# microBoard_DRV8842.net
KiCad netlist of a schematic drawn in EAGLE
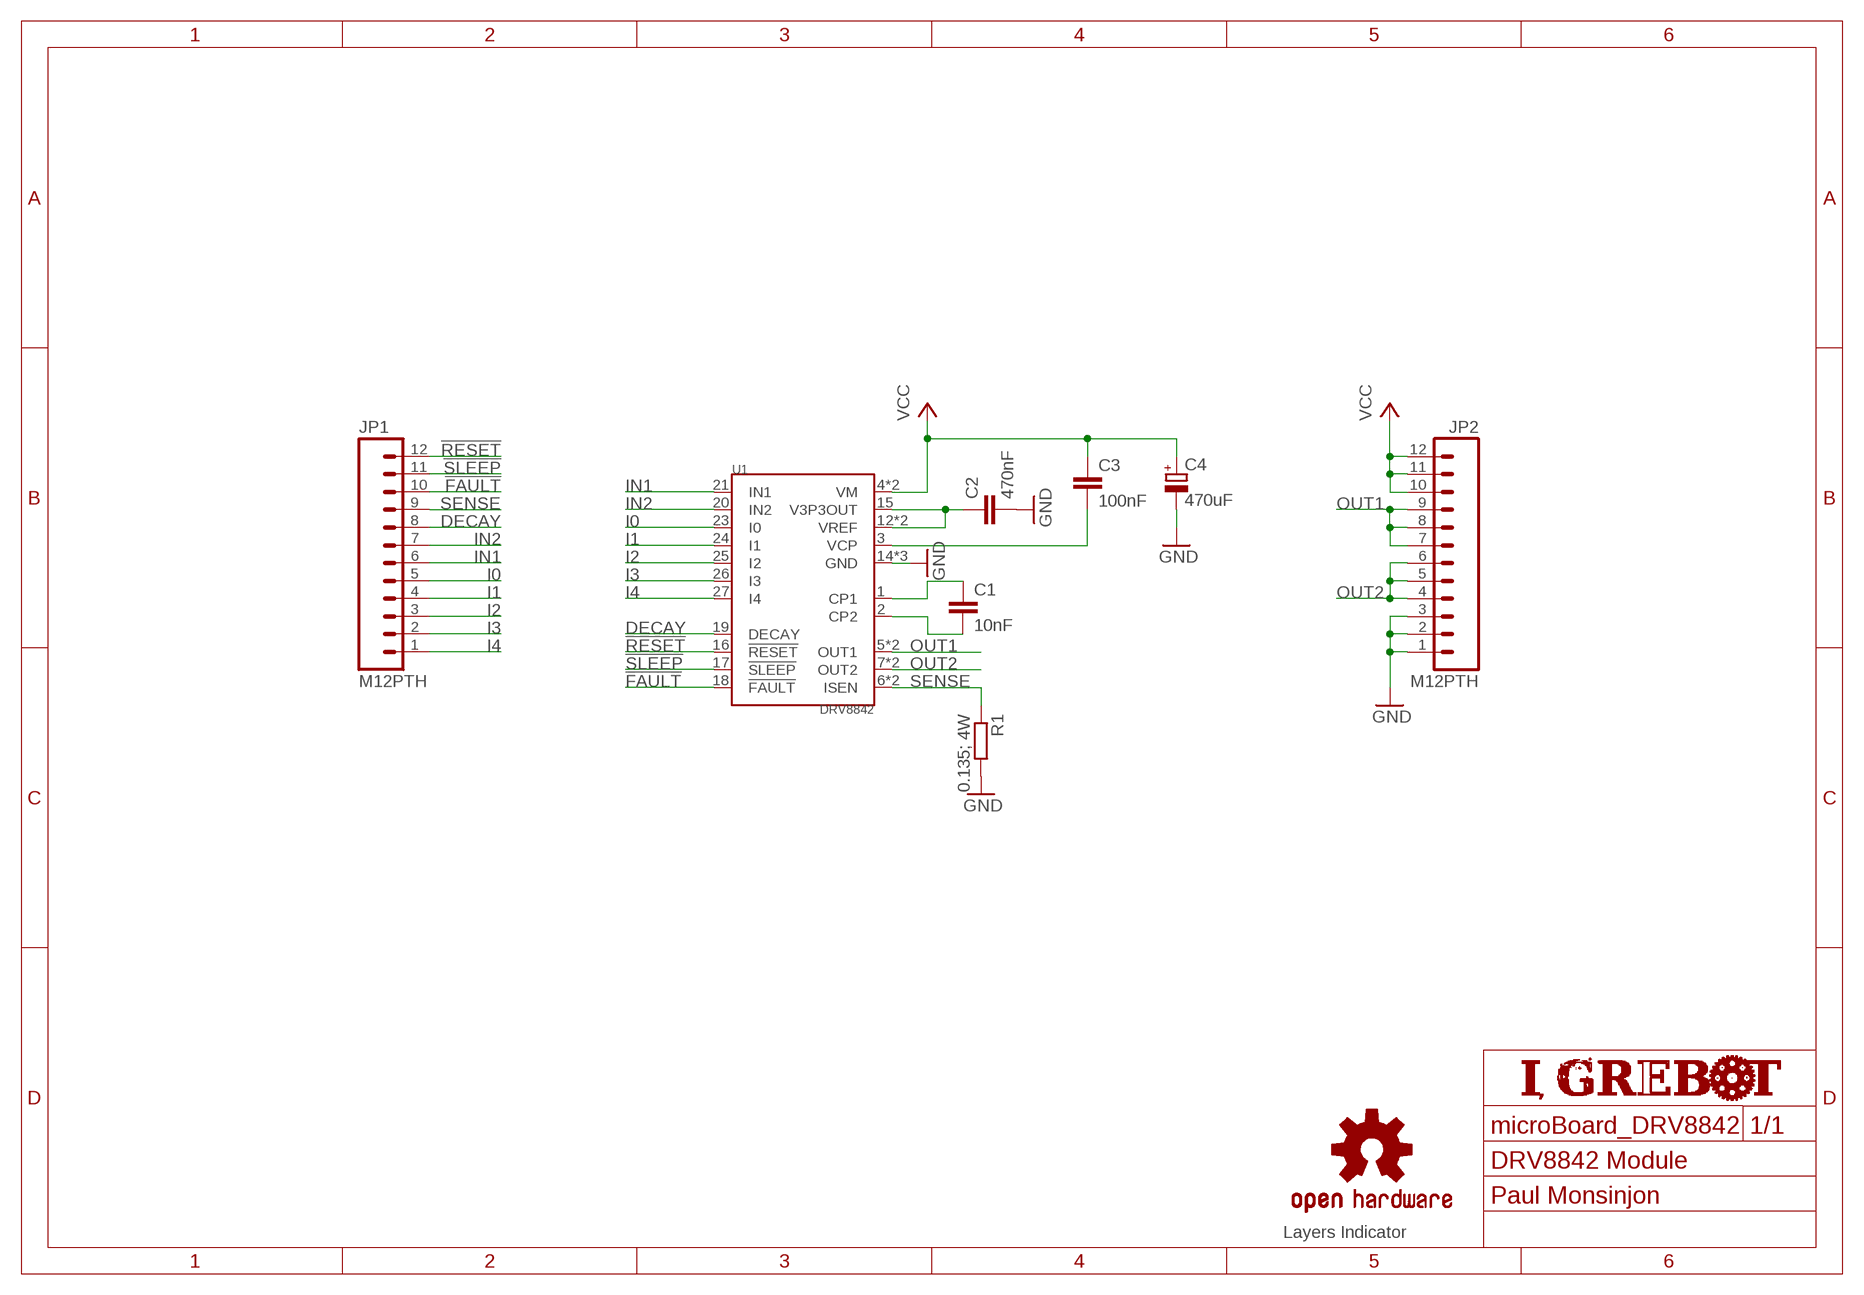
[diagram p0: schematic, sheet 1]

(export (version "E")
  (design (tool "Eeschema 10.0.6"))
  (components
    (comp (ref "C1")
      (value "10nF")
      (footprint "eagle-import:C0603")
      (libsource (lib "eagle-import") (part "C-EUC0603"))
    )
    (comp (ref "C2")
      (value "470nF")
      (footprint "eagle-import:C0603")
      (libsource (lib "eagle-import") (part "C-EUC0603"))
    )
    (comp (ref "C3")
      (value "100nF")
      (footprint "eagle-import:C0603")
      (libsource (lib "eagle-import") (part "C-EUC0603"))
    )
    (comp (ref "C4")
      (value "470uF")
      (footprint "eagle-import:PANASONIC_D")
      (libsource (lib "eagle-import") (part "CPOL-EUD"))
    )
    (comp (ref "JP1")
      (value "M12PTH")
      (footprint "eagle-import:1X12")
      (libsource (lib "eagle-import") (part "M12PTH"))
    )
    (comp (ref "JP2")
      (value "M12PTH")
      (footprint "eagle-import:1X12")
      (libsource (lib "eagle-import") (part "M12PTH"))
    )
    (comp (ref "LOGO1")
      (value "OSHW-LOGOS")
      (footprint "eagle-import:OSHW-LOGO-S")
      (libsource (lib "eagle-import") (part "OSHW-LOGOS"))
    )
    (comp (ref "R1")
      (value "0.135; 4W")
      (footprint "eagle-import:R2010")
      (libsource (lib "eagle-import") (part "R-EU_R2010"))
    )
    (comp (ref "U$1")
      (value "LOGO_IGREBOT12X2MM")
      (footprint "eagle-import:IGREBOT_12X2MM")
      (libsource (lib "eagle-import") (part "LOGO_IGREBOT12X2MM"))
    )
    (comp (ref "U$2")
      (value "LAYERS_CHECK4_LAYERS")
      (footprint "eagle-import:LAYERS_CHECK_4")
      (libsource (lib "eagle-import") (part "LAYERS_CHECK4_LAYERS"))
    )
    (comp (ref "U1")
      (value "DRV8842")
      (footprint "eagle-import:PWP_28")
      (libsource (lib "eagle-import") (part "DRV8842"))
    )
  )
  (nets
    (net (code "1") (name "/DECAY") (class "Default")
      (node (ref "JP1") (pin "8") (pinfunction "8_8") (pintype "passive"))
      (node (ref "U1") (pin "19") (pinfunction "DECAY_19") (pintype "bidirectional"))
    )
    (net (code "2") (name "/I0") (class "Default")
      (node (ref "JP1") (pin "5") (pinfunction "5_5") (pintype "passive"))
      (node (ref "U1") (pin "23") (pinfunction "I0_23") (pintype "bidirectional"))
    )
    (net (code "3") (name "/I1") (class "Default")
      (node (ref "JP1") (pin "4") (pinfunction "4_4") (pintype "passive"))
      (node (ref "U1") (pin "24") (pinfunction "I1_24") (pintype "bidirectional"))
    )
    (net (code "4") (name "/I2") (class "Default")
      (node (ref "JP1") (pin "3") (pinfunction "3_3") (pintype "passive"))
      (node (ref "U1") (pin "25") (pinfunction "I2_25") (pintype "bidirectional"))
    )
    (net (code "5") (name "/I3") (class "Default")
      (node (ref "JP1") (pin "2") (pinfunction "2_2") (pintype "passive"))
      (node (ref "U1") (pin "26") (pinfunction "I3_26") (pintype "bidirectional"))
    )
    (net (code "6") (name "/I4") (class "Default")
      (node (ref "JP1") (pin "1") (pinfunction "1_1") (pintype "passive"))
      (node (ref "U1") (pin "27") (pinfunction "I4_27") (pintype "bidirectional"))
    )
    (net (code "7") (name "/IN1") (class "Default")
      (node (ref "JP1") (pin "6") (pinfunction "6_6") (pintype "passive"))
      (node (ref "U1") (pin "21") (pinfunction "IN1_21") (pintype "bidirectional"))
    )
    (net (code "8") (name "/IN2") (class "Default")
      (node (ref "JP1") (pin "7") (pinfunction "7_7") (pintype "passive"))
      (node (ref "U1") (pin "20") (pinfunction "IN2_20") (pintype "bidirectional"))
    )
    (net (code "9") (name "/OUT1") (class "Default")
      (node (ref "JP2") (pin "7") (pinfunction "7_7") (pintype "passive"))
      (node (ref "JP2") (pin "8") (pinfunction "8_8") (pintype "passive"))
      (node (ref "JP2") (pin "9") (pinfunction "9_9") (pintype "passive"))
      (node (ref "U1") (pin "10") (pinfunction "OUT1_10") (pintype "bidirectional"))
      (node (ref "U1") (pin "5") (pinfunction "OUT1_5") (pintype "bidirectional"))
    )
    (net (code "10") (name "/OUT2") (class "Default")
      (node (ref "JP2") (pin "4") (pinfunction "4_4") (pintype "passive"))
      (node (ref "JP2") (pin "5") (pinfunction "5_5") (pintype "passive"))
      (node (ref "JP2") (pin "6") (pinfunction "6_6") (pintype "passive"))
      (node (ref "U1") (pin "7") (pinfunction "OUT2_7") (pintype "bidirectional"))
      (node (ref "U1") (pin "8") (pinfunction "OUT2_8") (pintype "bidirectional"))
    )
    (net (code "11") (name "/SENSE") (class "Default")
      (node (ref "JP1") (pin "9") (pinfunction "9_9") (pintype "passive"))
      (node (ref "R1") (pin "1") (pinfunction "1_1") (pintype "passive"))
      (node (ref "U1") (pin "6") (pinfunction "ISEN_6") (pintype "bidirectional"))
      (node (ref "U1") (pin "9") (pinfunction "ISEN_9") (pintype "bidirectional"))
    )
    (net (code "12") (name "/~{FAULT}") (class "Default")
      (node (ref "JP1") (pin "10") (pinfunction "10_10") (pintype "passive"))
      (node (ref "U1") (pin "18") (pinfunction "~{FAULT}_18") (pintype "bidirectional"))
    )
    (net (code "13") (name "/~{RESET}") (class "Default")
      (node (ref "JP1") (pin "12") (pinfunction "12_12") (pintype "passive"))
      (node (ref "U1") (pin "16") (pinfunction "~{RESET}_16") (pintype "bidirectional"))
    )
    (net (code "14") (name "/~{SLEEP}") (class "Default")
      (node (ref "JP1") (pin "11") (pinfunction "11_11") (pintype "passive"))
      (node (ref "U1") (pin "17") (pinfunction "~{SLEEP}_17") (pintype "bidirectional"))
    )
    (net (code "15") (name "GND") (class "Default")
      (node (ref "C2") (pin "2") (pinfunction "2_2") (pintype "passive"))
      (node (ref "C4") (pin "-") (pinfunction "-_-") (pintype "passive"))
      (node (ref "JP2") (pin "1") (pinfunction "1_1") (pintype "passive"))
      (node (ref "JP2") (pin "2") (pinfunction "2_2") (pintype "passive"))
      (node (ref "JP2") (pin "3") (pinfunction "3_3") (pintype "passive"))
      (node (ref "R1") (pin "2") (pinfunction "2_2") (pintype "passive"))
      (node (ref "U1") (pin "14") (pinfunction "GND_14") (pintype "power_in"))
      (node (ref "U1") (pin "28") (pinfunction "GND_28") (pintype "power_in"))
      (node (ref "U1") (pin "PPAD") (pinfunction "GND_PPAD") (pintype "power_in"))
    )
    (net (code "16") (name "Net-(U1-CP1)") (class "Default")
      (node (ref "C1") (pin "1") (pinfunction "1_1") (pintype "passive"))
      (node (ref "U1") (pin "1") (pinfunction "CP1_1") (pintype "bidirectional"))
    )
    (net (code "17") (name "Net-(U1-CP2)") (class "Default")
      (node (ref "C1") (pin "2") (pinfunction "2_2") (pintype "passive"))
      (node (ref "U1") (pin "2") (pinfunction "CP2_2") (pintype "bidirectional"))
    )
    (net (code "18") (name "Net-(U1-V3P3OUT)") (class "Default")
      (node (ref "C2") (pin "1") (pinfunction "1_1") (pintype "passive"))
      (node (ref "U1") (pin "12") (pinfunction "VREF_12") (pintype "bidirectional"))
      (node (ref "U1") (pin "13") (pinfunction "VREF_13") (pintype "bidirectional"))
      (node (ref "U1") (pin "15") (pinfunction "V3P3OUT_15") (pintype "power_in"))
    )
    (net (code "19") (name "Net-(U1-VCP)") (class "Default")
      (node (ref "C3") (pin "2") (pinfunction "2_2") (pintype "passive"))
      (node (ref "U1") (pin "3") (pinfunction "VCP_3") (pintype "passive"))
    )
    (net (code "20") (name "VCC") (class "Default")
      (node (ref "C3") (pin "1") (pinfunction "1_1") (pintype "passive"))
      (node (ref "C4") (pin "+") (pinfunction "+_+") (pintype "passive"))
      (node (ref "JP2") (pin "10") (pinfunction "10_10") (pintype "passive"))
      (node (ref "JP2") (pin "11") (pinfunction "11_11") (pintype "passive"))
      (node (ref "JP2") (pin "12") (pinfunction "12_12") (pintype "passive"))
      (node (ref "U1") (pin "11") (pinfunction "VM_11") (pintype "power_in"))
      (node (ref "U1") (pin "4") (pinfunction "VM_4") (pintype "power_in"))
    )
  )
)
